# Main.net
KiCad netlist of a schematic drawn in EAGLE
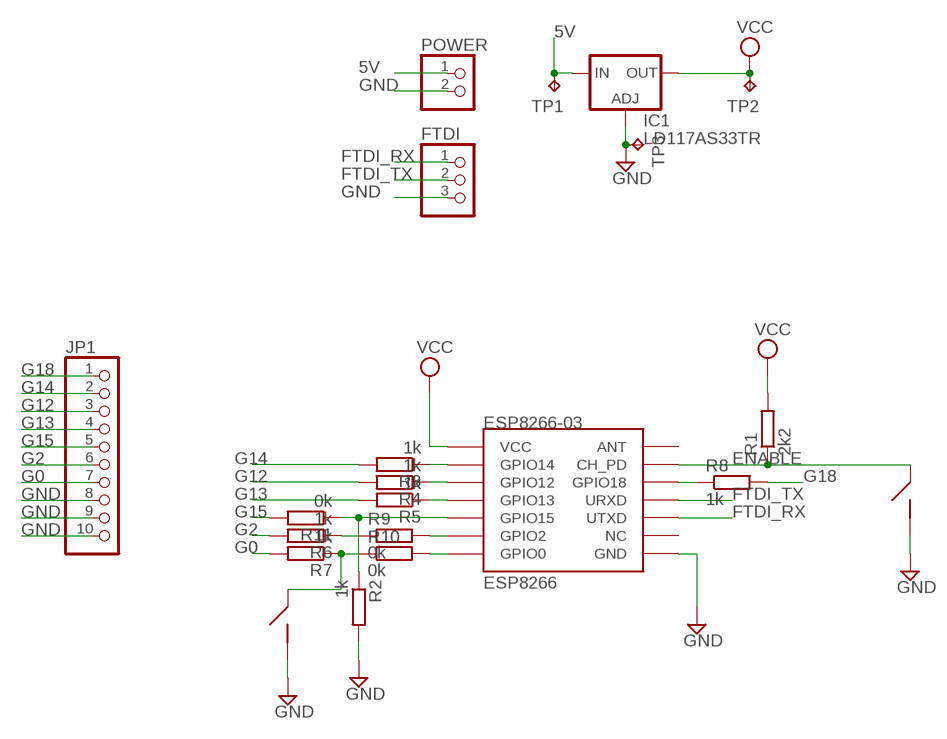
[diagram p0: schematic, sheet 1]

(export (version "E")
  (design (tool "Eeschema 10.0.6"))
  (components
    (comp (ref "ESP8266-03")
      (value "ESP8266")
      (footprint "eagle-import:ESP03")
      (libsource (lib "eagle-import") (part "ESP8266"))
    )
    (comp (ref "FTDI")
      (value "PINHD-1X3")
      (footprint "eagle-import:1X03")
      (libsource (lib "eagle-import") (part "PINHD-1X3"))
    )
    (comp (ref "IC1")
      (value "LD117AS33TR")
      (footprint "eagle-import:SOT223")
      (libsource (lib "eagle-import") (part "LD117A?S33TR"))
    )
    (comp (ref "JP1")
      (value "PINHD-1X10")
      (footprint "eagle-import:1X10")
      (libsource (lib "eagle-import") (part "PINHD-1X10"))
    )
    (comp (ref "POWER")
      (value "PINHD-1X2")
      (footprint "eagle-import:1X02")
      (libsource (lib "eagle-import") (part "PINHD-1X2"))
    )
    (comp (ref "R1")
      (value "2k2")
      (footprint "eagle-import:M0805")
      (libsource (lib "eagle-import") (part "R-EU_M0805"))
    )
    (comp (ref "R2")
      (value "1k")
      (footprint "eagle-import:M0805")
      (libsource (lib "eagle-import") (part "R-EU_M0805"))
    )
    (comp (ref "R3")
      (value "1k")
      (footprint "eagle-import:M0805")
      (libsource (lib "eagle-import") (part "R-EU_M0805"))
    )
    (comp (ref "R4")
      (value "1k")
      (footprint "eagle-import:M0805")
      (libsource (lib "eagle-import") (part "R-EU_M0805"))
    )
    (comp (ref "R5")
      (value "1k")
      (footprint "eagle-import:M0805")
      (libsource (lib "eagle-import") (part "R-EU_M0805"))
    )
    (comp (ref "R6")
      (value "1k")
      (footprint "eagle-import:M0805")
      (libsource (lib "eagle-import") (part "R-EU_M0805"))
    )
    (comp (ref "R7")
      (value "1k")
      (footprint "eagle-import:M0805")
      (libsource (lib "eagle-import") (part "R-EU_M0805"))
    )
    (comp (ref "R8")
      (value "1k")
      (footprint "eagle-import:M0805")
      (libsource (lib "eagle-import") (part "R-EU_M0805"))
    )
    (comp (ref "R9")
      (value "0k")
      (footprint "eagle-import:R1206")
      (libsource (lib "eagle-import") (part "R-EU_R1206"))
    )
    (comp (ref "R10")
      (value "0k")
      (footprint "eagle-import:R1206")
      (libsource (lib "eagle-import") (part "R-EU_R1206"))
    )
    (comp (ref "R11")
      (value "0k")
      (footprint "eagle-import:M0805")
      (libsource (lib "eagle-import") (part "R-EU_M0805"))
    )
    (comp (ref "TP1")
      (value "TPB1,27")
      (footprint "eagle-import:B1,27")
      (libsource (lib "eagle-import") (part "TPB1,27"))
    )
    (comp (ref "TP2")
      (value "TPB1,27")
      (footprint "eagle-import:B1,27")
      (libsource (lib "eagle-import") (part "TPB1,27"))
    )
    (comp (ref "TP3")
      (value "TPB1,27")
      (footprint "eagle-import:B1,27")
      (libsource (lib "eagle-import") (part "TPB1,27"))
    )
    (comp (ref "U$1")
      (value "TACTILE")
      (footprint "eagle-import:DTSM31N")
      (libsource (lib "eagle-import") (part "TACTILE"))
    )
    (comp (ref "U$2")
      (value "TACTILE")
      (footprint "eagle-import:DTSM31N")
      (libsource (lib "eagle-import") (part "TACTILE"))
    )
  )
  (nets
    (net (code "1") (name "/5V") (class "Default")
      (node (ref "IC1") (pin "3") (pinfunction "IN_3") (pintype "input"))
      (node (ref "POWER") (pin "1") (pinfunction "1_1") (pintype "passive"))
      (node (ref "TP1") (pin "TP") (pinfunction "TP_TP") (pintype "input"))
    )
    (net (code "2") (name "/ENABLE") (class "Default")
      (node (ref "ESP8266-03") (pin "CH_PD") (pinfunction "CH_PD_CH_PD") (pintype "bidirectional"))
      (node (ref "R1") (pin "1") (pinfunction "1_1") (pintype "passive"))
      (node (ref "U$2") (pin "P$1") (pinfunction "P$1_P$1") (pintype "bidirectional"))
    )
    (net (code "3") (name "/FTDI_RX") (class "Default")
      (node (ref "ESP8266-03") (pin "UTXD") (pinfunction "UTXD_UTXD") (pintype "bidirectional"))
      (node (ref "FTDI") (pin "1") (pinfunction "1_1") (pintype "passive"))
    )
    (net (code "4") (name "/FTDI_TX") (class "Default")
      (node (ref "ESP8266-03") (pin "URXD") (pinfunction "URXD_URXD") (pintype "bidirectional"))
      (node (ref "FTDI") (pin "2") (pinfunction "2_2") (pintype "passive"))
    )
    (net (code "5") (name "/G0") (class "Default")
      (node (ref "JP1") (pin "7") (pinfunction "7_7") (pintype "passive"))
      (node (ref "R7") (pin "2") (pinfunction "2_2") (pintype "passive"))
    )
    (net (code "6") (name "/G2") (class "Default")
      (node (ref "JP1") (pin "6") (pinfunction "6_6") (pintype "passive"))
      (node (ref "R6") (pin "2") (pinfunction "2_2") (pintype "passive"))
    )
    (net (code "7") (name "/G12") (class "Default")
      (node (ref "JP1") (pin "3") (pinfunction "3_3") (pintype "passive"))
      (node (ref "R4") (pin "2") (pinfunction "2_2") (pintype "passive"))
    )
    (net (code "8") (name "/G13") (class "Default")
      (node (ref "JP1") (pin "4") (pinfunction "4_4") (pintype "passive"))
      (node (ref "R5") (pin "2") (pinfunction "2_2") (pintype "passive"))
    )
    (net (code "9") (name "/G14") (class "Default")
      (node (ref "JP1") (pin "2") (pinfunction "2_2") (pintype "passive"))
      (node (ref "R3") (pin "2") (pinfunction "2_2") (pintype "passive"))
    )
    (net (code "10") (name "/G15") (class "Default")
      (node (ref "JP1") (pin "5") (pinfunction "5_5") (pintype "passive"))
      (node (ref "R11") (pin "2") (pinfunction "2_2") (pintype "passive"))
    )
    (net (code "11") (name "/G18") (class "Default")
      (node (ref "JP1") (pin "1") (pinfunction "1_1") (pintype "passive"))
      (node (ref "R8") (pin "2") (pinfunction "2_2") (pintype "passive"))
    )
    (net (code "12") (name "GND") (class "Default")
      (node (ref "ESP8266-03") (pin "GND") (pinfunction "GND_GND") (pintype "bidirectional"))
      (node (ref "FTDI") (pin "3") (pinfunction "3_3") (pintype "passive"))
      (node (ref "IC1") (pin "1") (pinfunction "ADJ_1") (pintype "input"))
      (node (ref "JP1") (pin "10") (pinfunction "10_10") (pintype "passive"))
      (node (ref "JP1") (pin "8") (pinfunction "8_8") (pintype "passive"))
      (node (ref "JP1") (pin "9") (pinfunction "9_9") (pintype "passive"))
      (node (ref "POWER") (pin "2") (pinfunction "2_2") (pintype "passive"))
      (node (ref "R2") (pin "2") (pinfunction "2_2") (pintype "passive"))
      (node (ref "TP3") (pin "TP") (pinfunction "TP_TP") (pintype "input"))
      (node (ref "U$1") (pin "P$2") (pinfunction "P$2_P$2") (pintype "bidirectional"))
      (node (ref "U$2") (pin "P$2") (pinfunction "P$2_P$2") (pintype "bidirectional"))
    )
    (net (code "13") (name "Net-(ESP8266-03-PadGPIO0)") (class "Default")
      (node (ref "ESP8266-03") (pin "GPIO0") (pinfunction "GPIO0_GPIO0") (pintype "bidirectional"))
      (node (ref "R10") (pin "2") (pinfunction "2_2") (pintype "passive"))
    )
    (net (code "14") (name "Net-(ESP8266-03-PadGPIO2)") (class "Default")
      (node (ref "ESP8266-03") (pin "GPIO2") (pinfunction "GPIO2_GPIO2") (pintype "bidirectional"))
      (node (ref "R9") (pin "2") (pinfunction "2_2") (pintype "passive"))
    )
    (net (code "15") (name "Net-(ESP8266-03-PadGPIO12)") (class "Default")
      (node (ref "ESP8266-03") (pin "GPIO12") (pinfunction "GPIO12_GPIO12") (pintype "bidirectional"))
      (node (ref "R4") (pin "1") (pinfunction "1_1") (pintype "passive"))
    )
    (net (code "16") (name "Net-(ESP8266-03-PadGPIO13)") (class "Default")
      (node (ref "ESP8266-03") (pin "GPIO13") (pinfunction "GPIO13_GPIO13") (pintype "bidirectional"))
      (node (ref "R5") (pin "1") (pinfunction "1_1") (pintype "passive"))
    )
    (net (code "17") (name "Net-(ESP8266-03-PadGPIO14)") (class "Default")
      (node (ref "ESP8266-03") (pin "GPIO14") (pinfunction "GPIO14_GPIO14") (pintype "bidirectional"))
      (node (ref "R3") (pin "1") (pinfunction "1_1") (pintype "passive"))
    )
    (net (code "18") (name "Net-(ESP8266-03-PadGPIO15)") (class "Default")
      (node (ref "ESP8266-03") (pin "GPIO15") (pinfunction "GPIO15_GPIO15") (pintype "bidirectional"))
      (node (ref "R11") (pin "1") (pinfunction "1_1") (pintype "passive"))
      (node (ref "R2") (pin "1") (pinfunction "1_1") (pintype "passive"))
    )
    (net (code "19") (name "Net-(ESP8266-03-PadGPIO18)") (class "Default")
      (node (ref "ESP8266-03") (pin "GPIO18") (pinfunction "GPIO18_GPIO18") (pintype "bidirectional"))
      (node (ref "R8") (pin "1") (pinfunction "1_1") (pintype "passive"))
    )
    (net (code "20") (name "Net-(R6-Pad1)") (class "Default")
      (node (ref "R6") (pin "1") (pinfunction "1_1") (pintype "passive"))
      (node (ref "R9") (pin "1") (pinfunction "1_1") (pintype "passive"))
    )
    (net (code "21") (name "Net-(R10-Pad1)") (class "Default")
      (node (ref "R10") (pin "1") (pinfunction "1_1") (pintype "passive"))
      (node (ref "R7") (pin "1") (pinfunction "1_1") (pintype "passive"))
      (node (ref "U$1") (pin "P$1") (pinfunction "P$1_P$1") (pintype "bidirectional"))
    )
    (net (code "22") (name "VCC") (class "Default")
      (node (ref "ESP8266-03") (pin "VCC") (pinfunction "VCC_VCC") (pintype "bidirectional"))
      (node (ref "IC1") (pin "4") (pinfunction "OUT_4") (pintype "passive"))
      (node (ref "R1") (pin "2") (pinfunction "2_2") (pintype "passive"))
      (node (ref "TP2") (pin "TP") (pinfunction "TP_TP") (pintype "input"))
    )
    (net (code "23") (name "unconnected-(ESP8266-03-PadANT)") (class "Default")
      (node (ref "ESP8266-03") (pin "ANT") (pinfunction "ANT_ANT") (pintype "bidirectional"))
    )
    (net (code "24") (name "unconnected-(ESP8266-03-PadNC)") (class "Default")
      (node (ref "ESP8266-03") (pin "NC") (pinfunction "NC_NC") (pintype "bidirectional"))
    )
  )
)
